# Sheet2.net
KiCad netlist of a schematic drawn in Altium Designer
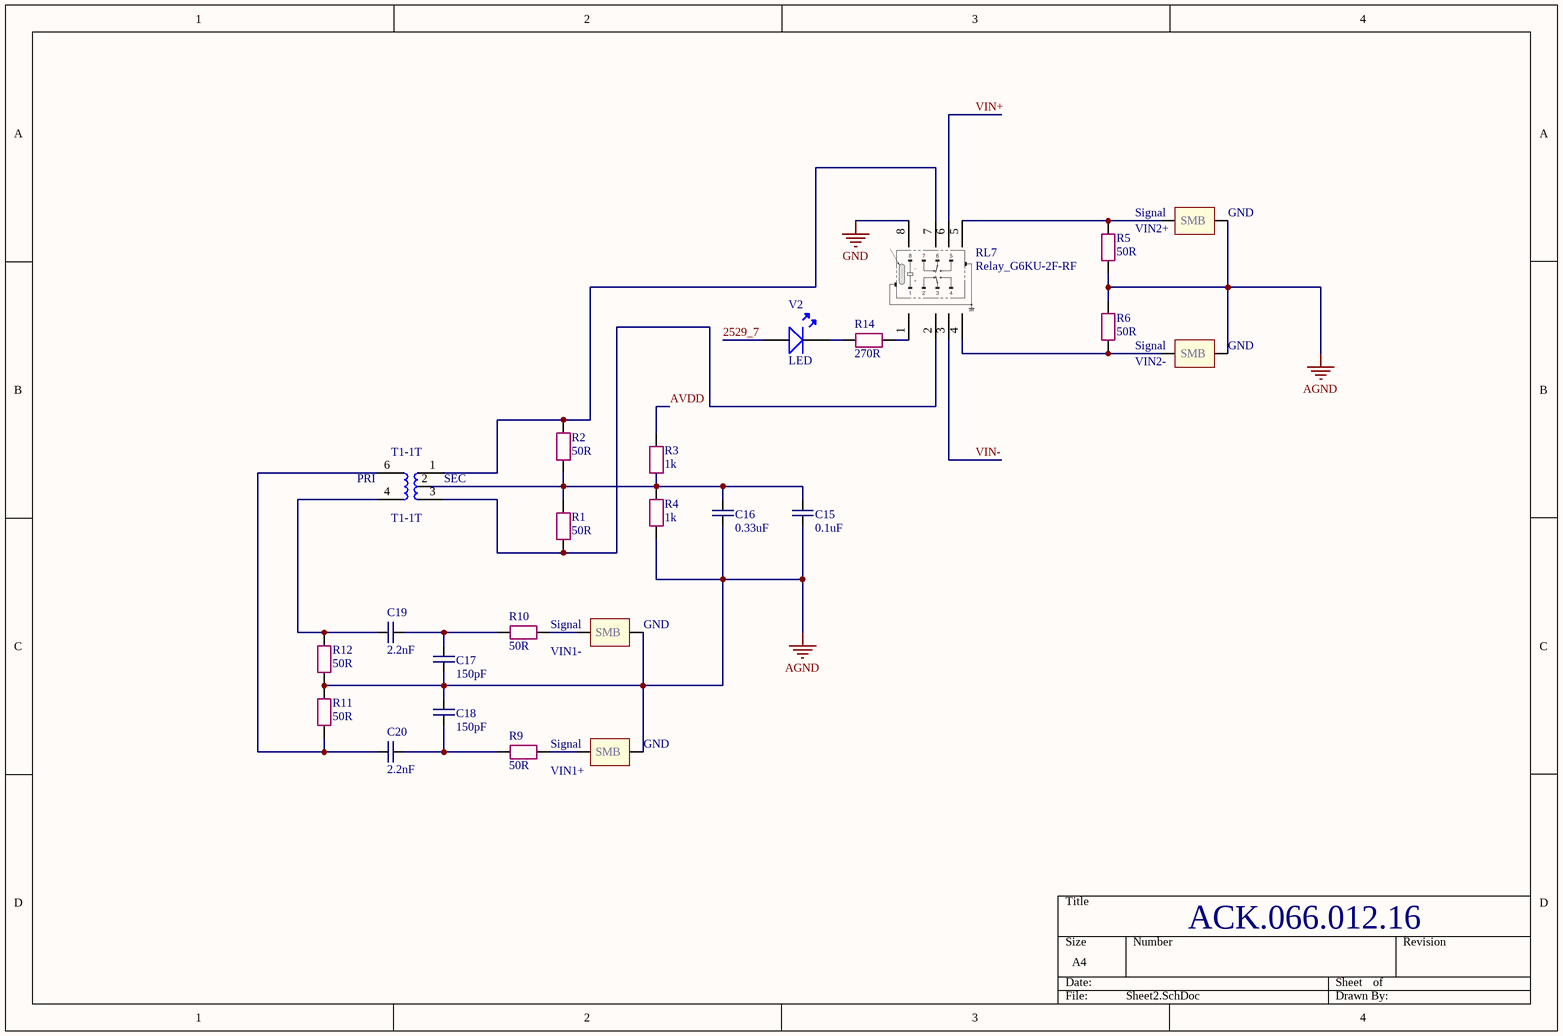
[diagram p0: Sheet2.SchDoc]

(export (version "E")
  (design (tool "Eeschema 10.0.6"))
  (components
    (comp (ref "C15")
      (value "0.1uF")
      (footprint "RCU:C_0805")
      (libsource (lib "RCU") (part "capacitor 0805"))
    )
    (comp (ref "C16")
      (value "0.33uF")
      (footprint "RCU:C_0805")
      (libsource (lib "RCU") (part "capacitor 0805"))
    )
    (comp (ref "C17")
      (value "150pF")
      (footprint "RCU:C_0805")
      (libsource (lib "RCU") (part "capacitor 0805"))
    )
    (comp (ref "C18")
      (value "150pF")
      (footprint "RCU:C_0805")
      (libsource (lib "RCU") (part "capacitor 0805"))
    )
    (comp (ref "C19")
      (value "2.2nF")
      (footprint "RCU:C_0805")
      (libsource (lib "RCU") (part "capacitor 0805"))
    )
    (comp (ref "C20")
      (value "2.2nF")
      (footprint "RCU:C_0805")
      (libsource (lib "RCU") (part "capacitor 0805"))
    )
    (comp (ref "R1") (value "50R") (footprint "RCU:R_0805") (libsource (lib "RCU") (part "resistor 0805")))
    (comp (ref "R2") (value "50R") (footprint "RCU:R_0805") (libsource (lib "RCU") (part "resistor 0805")))
    (comp (ref "R3") (value "1k") (footprint "RCU:R_0805") (libsource (lib "RCU") (part "resistor 0805")))
    (comp (ref "R4") (value "1k") (footprint "RCU:R_0805") (libsource (lib "RCU") (part "resistor 0805")))
    (comp (ref "R5") (value "50R") (footprint "RCU:R_0805") (libsource (lib "RCU") (part "resistor 0805")))
    (comp (ref "R6") (value "50R") (footprint "RCU:R_0805") (libsource (lib "RCU") (part "resistor 0805")))
    (comp (ref "R9") (value "50R") (footprint "RCU:R_0805") (libsource (lib "RCU") (part "resistor 0805")))
    (comp (ref "R10") (value "50R") (footprint "RCU:R_0805") (libsource (lib "RCU") (part "resistor 0805")))
    (comp (ref "R11") (value "50R") (footprint "RCU:R_0805") (libsource (lib "RCU") (part "resistor 0805")))
    (comp (ref "R12") (value "50R") (footprint "RCU:R_0805") (libsource (lib "RCU") (part "resistor 0805")))
    (comp (ref "R14") (value "270R") (footprint "RCU:R_0805") (libsource (lib "RCU") (part "resistor 0805")))
    (comp (ref "RL7")
      (value "Relay_G6KU-2F-RF")
      (footprint "Relay_G6KU-2F-RF")
      (libsource (lib "RCU") (part "Relay_G6KU-2F-RF"))
    )
    (comp (ref "T1-1T") (value "T1-1T") (footprint "T1-1T") (libsource (lib "RCU") (part "T1-1T")))
    (comp (ref "V2") (value "LED") (footprint "LED") (libsource (lib "RCU") (part "LED")))
    (comp (ref "VIN1+") (value "SMB") (footprint "RCU:SMB") (libsource (lib "RCU") (part "SMB")))
    (comp (ref "VIN1-") (value "SMB") (footprint "RCU:SMB") (libsource (lib "RCU") (part "SMB")))
    (comp (ref "VIN2+") (value "SMB") (footprint "RCU:SMB") (libsource (lib "RCU") (part "SMB")))
    (comp (ref "VIN2-") (value "SMB") (footprint "RCU:SMB") (libsource (lib "RCU") (part "SMB")))
  )
  (nets
    (net (code "1") (name "/2529_7") (class "Default")
      (node (ref "V2") (pin "1") (pinfunction "1_1") (pintype "passive"))
    )
    (net (code "2") (name "/AVDD") (class "Default")
      (node (ref "R3") (pin "2") (pinfunction "2_2") (pintype "passive"))
    )
    (net (code "3") (name "/VIN+") (class "Default")
      (node (ref "RL7") (pin "6") (pinfunction "6_6") (pintype "passive"))
    )
    (net (code "4") (name "/VIN-") (class "Default")
      (node (ref "RL7") (pin "3") (pinfunction "3_3") (pintype "passive"))
    )
    (net (code "5") (name "AGND") (class "Default")
      (node (ref "C15") (pin "1") (pinfunction "1_1") (pintype "passive"))
      (node (ref "C16") (pin "1") (pinfunction "1_1") (pintype "passive"))
      (node (ref "C17") (pin "1") (pinfunction "1_1") (pintype "passive"))
      (node (ref "C18") (pin "2") (pinfunction "2_2") (pintype "passive"))
      (node (ref "R11") (pin "2") (pinfunction "2_2") (pintype "passive"))
      (node (ref "R12") (pin "1") (pinfunction "1_1") (pintype "passive"))
      (node (ref "R4") (pin "1") (pinfunction "1_1") (pintype "passive"))
      (node (ref "R5") (pin "1") (pinfunction "1_1") (pintype "passive"))
      (node (ref "R6") (pin "2") (pinfunction "2_2") (pintype "passive"))
      (node (ref "VIN1+") (pin "0") (pinfunction "0_0") (pintype "passive"))
      (node (ref "VIN1-") (pin "0") (pinfunction "0_0") (pintype "passive"))
      (node (ref "VIN2+") (pin "0") (pinfunction "0_0") (pintype "passive"))
      (node (ref "VIN2-") (pin "0") (pinfunction "0_0") (pintype "passive"))
    )
    (net (code "6") (name "GND") (class "Default")
      (node (ref "RL7") (pin "8") (pinfunction "8_8") (pintype "passive"))
    )
    (net (code "7") (name "Net-(C17-Pad2)") (class "Default")
      (node (ref "C17") (pin "2") (pinfunction "2_2") (pintype "passive"))
      (node (ref "C19") (pin "1") (pinfunction "1_1") (pintype "passive"))
      (node (ref "R10") (pin "1") (pinfunction "1_1") (pintype "passive"))
    )
    (net (code "8") (name "Net-(C18-Pad1)") (class "Default")
      (node (ref "C18") (pin "1") (pinfunction "1_1") (pintype "passive"))
      (node (ref "C20") (pin "1") (pinfunction "1_1") (pintype "passive"))
      (node (ref "R9") (pin "1") (pinfunction "1_1") (pintype "passive"))
    )
    (net (code "9") (name "Net-(R5-Pad2)") (class "Default")
      (node (ref "R5") (pin "2") (pinfunction "2_2") (pintype "passive"))
      (node (ref "RL7") (pin "5") (pinfunction "5_5") (pintype "passive"))
      (node (ref "VIN2+") (pin "1") (pinfunction "1_1") (pintype "passive"))
    )
    (net (code "10") (name "Net-(R6-Pad1)") (class "Default")
      (node (ref "R6") (pin "1") (pinfunction "1_1") (pintype "passive"))
      (node (ref "RL7") (pin "4") (pinfunction "4_4") (pintype "passive"))
      (node (ref "VIN2-") (pin "1") (pinfunction "1_1") (pintype "passive"))
    )
    (net (code "11") (name "Net-(R9-Pad2)") (class "Default")
      (node (ref "R9") (pin "2") (pinfunction "2_2") (pintype "passive"))
      (node (ref "VIN1+") (pin "1") (pinfunction "1_1") (pintype "passive"))
    )
    (net (code "12") (name "Net-(R10-Pad2)") (class "Default")
      (node (ref "R10") (pin "2") (pinfunction "2_2") (pintype "passive"))
      (node (ref "VIN1-") (pin "1") (pinfunction "1_1") (pintype "passive"))
    )
    (net (code "13") (name "Net-(R14-Pad1)") (class "Default")
      (node (ref "R14") (pin "1") (pinfunction "1_1") (pintype "passive"))
      (node (ref "RL7") (pin "1") (pinfunction "1_1") (pintype "passive"))
    )
    (net (code "14") (name "Net-(R14-Pad2)") (class "Default")
      (node (ref "R14") (pin "2") (pinfunction "2_2") (pintype "passive"))
      (node (ref "V2") (pin "2") (pinfunction "2_2") (pintype "passive"))
    )
    (net (code "15") (name "Net-(T1-1T-PRIM)") (class "Default")
      (node (ref "C20") (pin "2") (pinfunction "2_2") (pintype "passive"))
      (node (ref "R11") (pin "1") (pinfunction "1_1") (pintype "passive"))
      (node (ref "T1-1T") (pin "6") (pinfunction "PRIM_6") (pintype "passive"))
    )
    (net (code "16") (name "Net-(T1-1T-PRIM_DOT)") (class "Default")
      (node (ref "C19") (pin "2") (pinfunction "2_2") (pintype "passive"))
      (node (ref "R12") (pin "2") (pinfunction "2_2") (pintype "passive"))
      (node (ref "T1-1T") (pin "4") (pinfunction "PRIM_DOT_4") (pintype "passive"))
    )
    (net (code "17") (name "Net-(T1-1T-SEC)") (class "Default")
      (node (ref "R2") (pin "2") (pinfunction "2_2") (pintype "passive"))
      (node (ref "RL7") (pin "7") (pinfunction "7_7") (pintype "passive"))
      (node (ref "T1-1T") (pin "1") (pinfunction "SEC_1") (pintype "passive"))
    )
    (net (code "18") (name "Net-(T1-1T-SEC_CT)") (class "Default")
      (node (ref "C15") (pin "2") (pinfunction "2_2") (pintype "passive"))
      (node (ref "C16") (pin "2") (pinfunction "2_2") (pintype "passive"))
      (node (ref "R1") (pin "2") (pinfunction "2_2") (pintype "passive"))
      (node (ref "R2") (pin "1") (pinfunction "1_1") (pintype "passive"))
      (node (ref "R3") (pin "1") (pinfunction "1_1") (pintype "passive"))
      (node (ref "R4") (pin "2") (pinfunction "2_2") (pintype "passive"))
      (node (ref "T1-1T") (pin "2") (pinfunction "SEC_CT_2") (pintype "passive"))
    )
    (net (code "19") (name "Net-(T1-1T-SEC_DOT)") (class "Default")
      (node (ref "R1") (pin "1") (pinfunction "1_1") (pintype "passive"))
      (node (ref "RL7") (pin "2") (pinfunction "2_2") (pintype "passive"))
      (node (ref "T1-1T") (pin "3") (pinfunction "SEC_DOT_3") (pintype "passive"))
    )
  )
)
